# SCH_mosfet_driver_copy_2022-10-09.net
KiCad netlist of a schematic drawn in EasyEDA
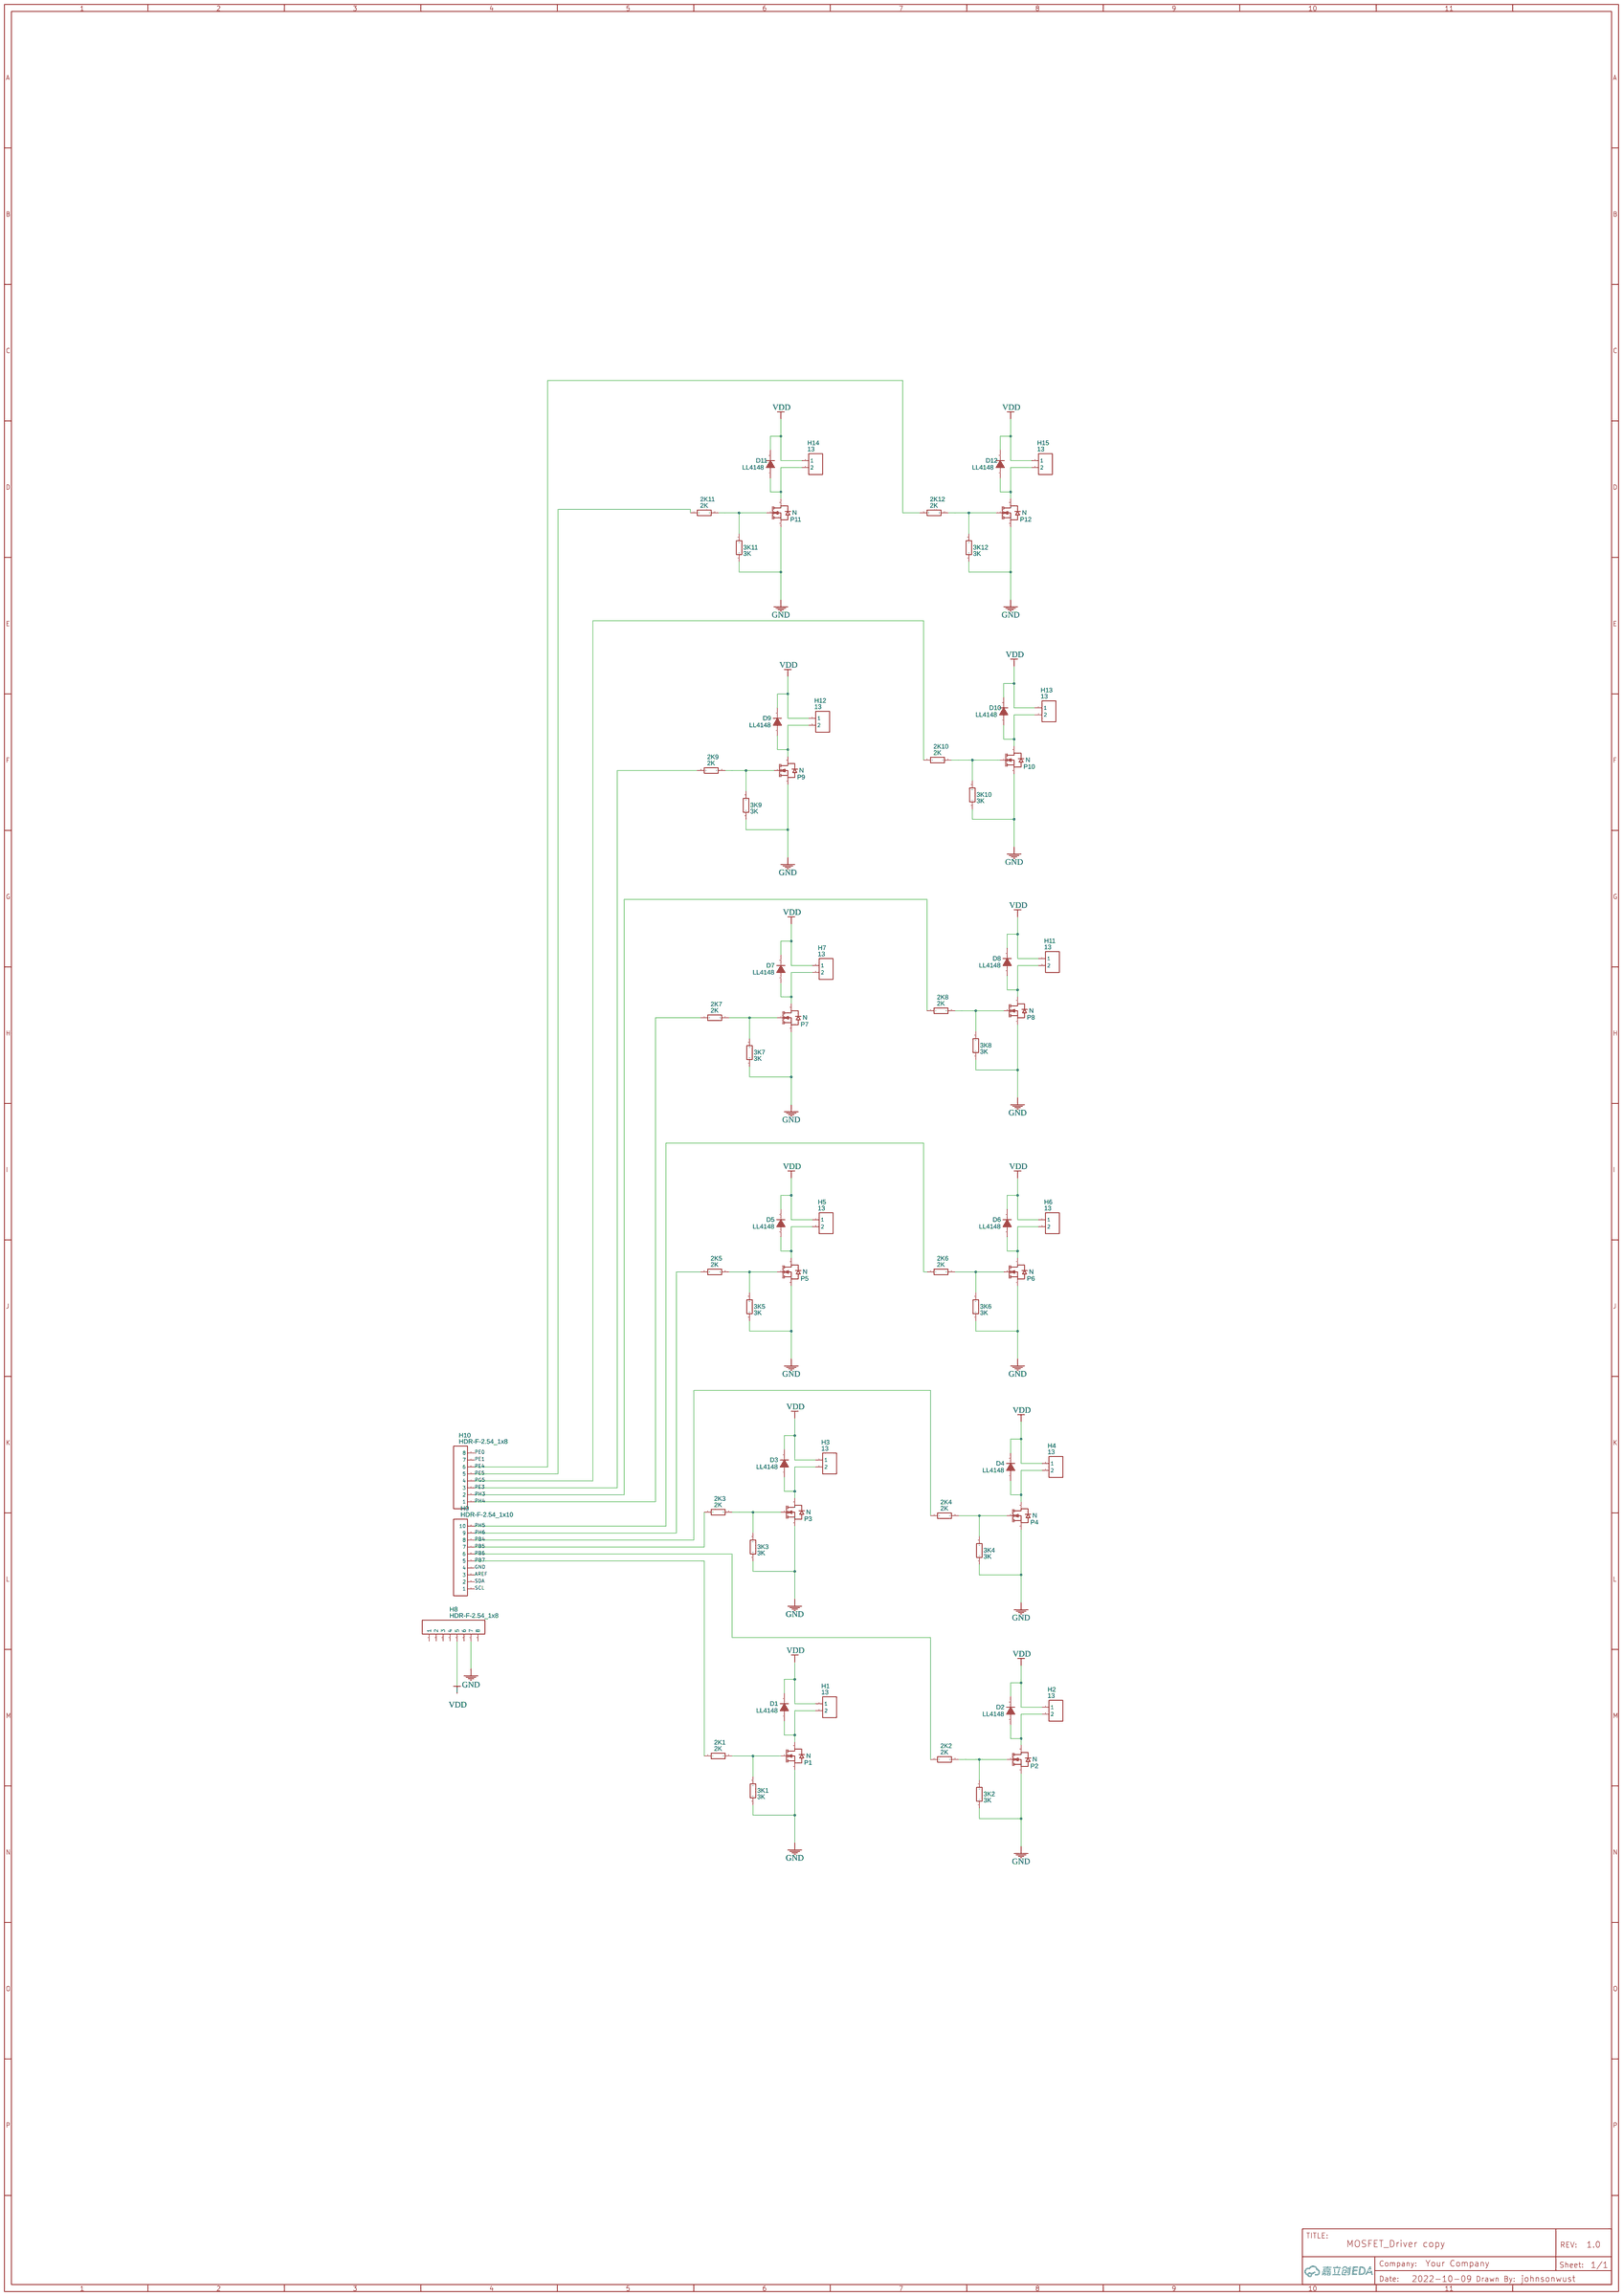
[diagram p0: schematic sheet]

(export (version "E")
  (design (tool "Eeschema 10.0.6"))
  (components
    (comp (ref "2K1")
      (value "2K")
      (fields
        (field (name "BOM_Manufacturer Part") "0805W8F1003T5E")
        (field (name "BOM_Supplier Part") "C17407")
      )
      (libsource (lib "") (part "0805W8F1003T5E"))
    )
    (comp (ref "2K2")
      (value "2K")
      (fields
        (field (name "BOM_Manufacturer Part") "0805W8F1003T5E")
        (field (name "BOM_Supplier Part") "C17407")
      )
      (libsource (lib "") (part "0805W8F1003T5E"))
    )
    (comp (ref "2K3")
      (value "2K")
      (fields
        (field (name "BOM_Manufacturer Part") "0805W8F1003T5E")
        (field (name "BOM_Supplier Part") "C17407")
      )
      (libsource (lib "") (part "0805W8F1003T5E"))
    )
    (comp (ref "2K4")
      (value "2K")
      (fields
        (field (name "BOM_Manufacturer Part") "0805W8F1003T5E")
        (field (name "BOM_Supplier Part") "C17407")
      )
      (libsource (lib "") (part "0805W8F1003T5E"))
    )
    (comp (ref "2K5")
      (value "2K")
      (fields
        (field (name "BOM_Manufacturer Part") "0805W8F1003T5E")
        (field (name "BOM_Supplier Part") "C17407")
      )
      (libsource (lib "") (part "0805W8F1003T5E"))
    )
    (comp (ref "2K6")
      (value "2K")
      (fields
        (field (name "BOM_Manufacturer Part") "0805W8F1003T5E")
        (field (name "BOM_Supplier Part") "C17407")
      )
      (libsource (lib "") (part "0805W8F1003T5E"))
    )
    (comp (ref "2K7")
      (value "2K")
      (fields
        (field (name "BOM_Manufacturer Part") "0805W8F1003T5E")
        (field (name "BOM_Supplier Part") "C17407")
      )
      (libsource (lib "") (part "0805W8F1003T5E"))
    )
    (comp (ref "2K8")
      (value "2K")
      (fields
        (field (name "BOM_Manufacturer Part") "0805W8F1003T5E")
        (field (name "BOM_Supplier Part") "C17407")
      )
      (libsource (lib "") (part "0805W8F1003T5E"))
    )
    (comp (ref "2K9")
      (value "2K")
      (fields
        (field (name "BOM_Manufacturer Part") "0805W8F1003T5E")
        (field (name "BOM_Supplier Part") "C17407")
      )
      (libsource (lib "") (part "0805W8F1003T5E"))
    )
    (comp (ref "2K10")
      (value "2K")
      (fields
        (field (name "BOM_Manufacturer Part") "0805W8F1003T5E")
        (field (name "BOM_Supplier Part") "C17407")
      )
      (libsource (lib "") (part "0805W8F1003T5E"))
    )
    (comp (ref "2K11")
      (value "2K")
      (fields
        (field (name "BOM_Manufacturer Part") "0805W8F1003T5E")
        (field (name "BOM_Supplier Part") "C17407")
      )
      (libsource (lib "") (part "0805W8F1003T5E"))
    )
    (comp (ref "2K12")
      (value "2K")
      (fields
        (field (name "BOM_Manufacturer Part") "0805W8F1003T5E")
        (field (name "BOM_Supplier Part") "C17407")
      )
      (libsource (lib "") (part "0805W8F1003T5E"))
    )
    (comp (ref "3K1")
      (value "3K")
      (fields
        (field (name "BOM_Manufacturer Part") "0805W8F1001T5E")
        (field (name "BOM_Supplier Part") "C17513")
      )
      (libsource (lib "") (part "0805W8F1001T5E"))
    )
    (comp (ref "3K2")
      (value "3K")
      (fields
        (field (name "BOM_Manufacturer Part") "0805W8F1001T5E")
        (field (name "BOM_Supplier Part") "C17513")
      )
      (libsource (lib "") (part "0805W8F1001T5E"))
    )
    (comp (ref "3K3")
      (value "3K")
      (fields
        (field (name "BOM_Manufacturer Part") "0805W8F1001T5E")
        (field (name "BOM_Supplier Part") "C17513")
      )
      (libsource (lib "") (part "0805W8F1001T5E"))
    )
    (comp (ref "3K4")
      (value "3K")
      (fields
        (field (name "BOM_Manufacturer Part") "0805W8F1001T5E")
        (field (name "BOM_Supplier Part") "C17513")
      )
      (libsource (lib "") (part "0805W8F1001T5E"))
    )
    (comp (ref "3K5")
      (value "3K")
      (fields
        (field (name "BOM_Manufacturer Part") "0805W8F1001T5E")
        (field (name "BOM_Supplier Part") "C17513")
      )
      (libsource (lib "") (part "0805W8F1001T5E"))
    )
    (comp (ref "3K6")
      (value "3K")
      (fields
        (field (name "BOM_Manufacturer Part") "0805W8F1001T5E")
        (field (name "BOM_Supplier Part") "C17513")
      )
      (libsource (lib "") (part "0805W8F1001T5E"))
    )
    (comp (ref "3K7")
      (value "3K")
      (fields
        (field (name "BOM_Manufacturer Part") "0805W8F1001T5E")
        (field (name "BOM_Supplier Part") "C17513")
      )
      (libsource (lib "") (part "0805W8F1001T5E"))
    )
    (comp (ref "3K8")
      (value "3K")
      (fields
        (field (name "BOM_Manufacturer Part") "0805W8F1001T5E")
        (field (name "BOM_Supplier Part") "C17513")
      )
      (libsource (lib "") (part "0805W8F1001T5E"))
    )
    (comp (ref "3K9")
      (value "3K")
      (fields
        (field (name "BOM_Manufacturer Part") "0805W8F1001T5E")
        (field (name "BOM_Supplier Part") "C17513")
      )
      (libsource (lib "") (part "0805W8F1001T5E"))
    )
    (comp (ref "3K10")
      (value "3K")
      (fields
        (field (name "BOM_Manufacturer Part") "0805W8F1001T5E")
        (field (name "BOM_Supplier Part") "C17513")
      )
      (libsource (lib "") (part "0805W8F1001T5E"))
    )
    (comp (ref "3K11")
      (value "3K")
      (fields
        (field (name "BOM_Manufacturer Part") "0805W8F1001T5E")
        (field (name "BOM_Supplier Part") "C17513")
      )
      (libsource (lib "") (part "0805W8F1001T5E"))
    )
    (comp (ref "3K12")
      (value "3K")
      (fields
        (field (name "BOM_Manufacturer Part") "0805W8F1001T5E")
        (field (name "BOM_Supplier Part") "C17513")
      )
      (libsource (lib "") (part "0805W8F1001T5E"))
    )
    (comp (ref "D1")
      (value "LL4148")
      (fields (field (name "BOM_Supplier Part") "C9808"))
      (libsource (lib "") (part "LL4148"))
    )
    (comp (ref "D2")
      (value "LL4148")
      (fields (field (name "BOM_Supplier Part") "C9808"))
      (libsource (lib "") (part "LL4148"))
    )
    (comp (ref "D3")
      (value "LL4148")
      (fields (field (name "BOM_Supplier Part") "C9808"))
      (libsource (lib "") (part "LL4148"))
    )
    (comp (ref "D4")
      (value "LL4148")
      (fields (field (name "BOM_Supplier Part") "C9808"))
      (libsource (lib "") (part "LL4148"))
    )
    (comp (ref "D5")
      (value "LL4148")
      (fields (field (name "BOM_Supplier Part") "C9808"))
      (libsource (lib "") (part "LL4148"))
    )
    (comp (ref "D6")
      (value "LL4148")
      (fields (field (name "BOM_Supplier Part") "C9808"))
      (libsource (lib "") (part "LL4148"))
    )
    (comp (ref "D7")
      (value "LL4148")
      (fields (field (name "BOM_Supplier Part") "C9808"))
      (libsource (lib "") (part "LL4148"))
    )
    (comp (ref "D8")
      (value "LL4148")
      (fields (field (name "BOM_Supplier Part") "C9808"))
      (libsource (lib "") (part "LL4148"))
    )
    (comp (ref "D9")
      (value "LL4148")
      (fields (field (name "BOM_Supplier Part") "C9808"))
      (libsource (lib "") (part "LL4148"))
    )
    (comp (ref "D10")
      (value "LL4148")
      (fields (field (name "BOM_Supplier Part") "C9808"))
      (libsource (lib "") (part "LL4148"))
    )
    (comp (ref "D11")
      (value "LL4148")
      (fields (field (name "BOM_Supplier Part") "C9808"))
      (libsource (lib "") (part "LL4148"))
    )
    (comp (ref "D12")
      (value "LL4148")
      (fields (field (name "BOM_Supplier Part") "C9808"))
      (libsource (lib "") (part "LL4148"))
    )
    (comp (ref "H1")
      (value "13")
      (fields (field (name "BOM_Supplier Part") "C49661"))
      (libsource (lib "") (part "HDR-F-2.54_1x2"))
    )
    (comp (ref "H2")
      (value "13")
      (fields (field (name "BOM_Supplier Part") "C49661"))
      (libsource (lib "") (part "HDR-F-2.54_1x2"))
    )
    (comp (ref "H3")
      (value "13")
      (fields (field (name "BOM_Supplier Part") "C49661"))
      (libsource (lib "") (part "HDR-F-2.54_1x2"))
    )
    (comp (ref "H4")
      (value "13")
      (fields (field (name "BOM_Supplier Part") "C49661"))
      (libsource (lib "") (part "HDR-F-2.54_1x2"))
    )
    (comp (ref "H5")
      (value "13")
      (fields (field (name "BOM_Supplier Part") "C49661"))
      (libsource (lib "") (part "HDR-F-2.54_1x2"))
    )
    (comp (ref "H6")
      (value "13")
      (fields (field (name "BOM_Supplier Part") "C49661"))
      (libsource (lib "") (part "HDR-F-2.54_1x2"))
    )
    (comp (ref "H7")
      (value "13")
      (fields (field (name "BOM_Supplier Part") "C49661"))
      (libsource (lib "") (part "HDR-F-2.54_1x2"))
    )
    (comp (ref "H8")
      (value "HDR-F-2.54_1x8")
      (fields (field (name "BOM_Supplier Part") "C225505"))
      (libsource (lib "") (part "HDR-F-2.54_1x8"))
    )
    (comp (ref "H9")
      (value "HDR-F-2.54_1x10")
      (fields (field (name "BOM_Supplier Part") "C35445"))
      (libsource (lib "") (part "HDR-F-2.54_1x10"))
    )
    (comp (ref "H10")
      (value "HDR-F-2.54_1x8")
      (fields (field (name "BOM_Supplier Part") "C225505"))
      (libsource (lib "") (part "HDR-F-2.54_1x8_1"))
    )
    (comp (ref "H11")
      (value "13")
      (fields (field (name "BOM_Supplier Part") "C49661"))
      (libsource (lib "") (part "HDR-F-2.54_1x2"))
    )
    (comp (ref "H12")
      (value "13")
      (fields (field (name "BOM_Supplier Part") "C49661"))
      (libsource (lib "") (part "HDR-F-2.54_1x2"))
    )
    (comp (ref "H13")
      (value "13")
      (fields (field (name "BOM_Supplier Part") "C49661"))
      (libsource (lib "") (part "HDR-F-2.54_1x2"))
    )
    (comp (ref "H14")
      (value "13")
      (fields (field (name "BOM_Supplier Part") "C49661"))
      (libsource (lib "") (part "HDR-F-2.54_1x2"))
    )
    (comp (ref "H15")
      (value "13")
      (fields (field (name "BOM_Supplier Part") "C49661"))
      (libsource (lib "") (part "HDR-F-2.54_1x2"))
    )
    (comp (ref "P1")
      (value "N")
      (fields (field (name "BOM_Manufacturer Part") "BSS138") (field (name "BOM_Supplier Part") "C779768"))
      (libsource (lib "") (part "BSS138_C779768"))
    )
    (comp (ref "P2")
      (value "N")
      (fields (field (name "BOM_Manufacturer Part") "BSS138") (field (name "BOM_Supplier Part") "C779768"))
      (libsource (lib "") (part "BSS138_C779768"))
    )
    (comp (ref "P3")
      (value "N")
      (fields (field (name "BOM_Manufacturer Part") "BSS138") (field (name "BOM_Supplier Part") "C779768"))
      (libsource (lib "") (part "BSS138_C779768"))
    )
    (comp (ref "P4")
      (value "N")
      (fields (field (name "BOM_Manufacturer Part") "BSS138") (field (name "BOM_Supplier Part") "C779768"))
      (libsource (lib "") (part "BSS138_C779768"))
    )
    (comp (ref "P5")
      (value "N")
      (fields (field (name "BOM_Manufacturer Part") "BSS138") (field (name "BOM_Supplier Part") "C779768"))
      (libsource (lib "") (part "BSS138_C779768"))
    )
    (comp (ref "P6")
      (value "N")
      (fields (field (name "BOM_Manufacturer Part") "BSS138") (field (name "BOM_Supplier Part") "C779768"))
      (libsource (lib "") (part "BSS138_C779768"))
    )
    (comp (ref "P7")
      (value "N")
      (fields (field (name "BOM_Manufacturer Part") "BSS138") (field (name "BOM_Supplier Part") "C779768"))
      (libsource (lib "") (part "BSS138_C779768"))
    )
    (comp (ref "P8")
      (value "N")
      (fields (field (name "BOM_Manufacturer Part") "BSS138") (field (name "BOM_Supplier Part") "C779768"))
      (libsource (lib "") (part "BSS138_C779768"))
    )
    (comp (ref "P9")
      (value "N")
      (fields (field (name "BOM_Manufacturer Part") "BSS138") (field (name "BOM_Supplier Part") "C779768"))
      (libsource (lib "") (part "BSS138_C779768"))
    )
    (comp (ref "P10")
      (value "N")
      (fields (field (name "BOM_Manufacturer Part") "BSS138") (field (name "BOM_Supplier Part") "C779768"))
      (libsource (lib "") (part "BSS138_C779768"))
    )
    (comp (ref "P11")
      (value "N")
      (fields (field (name "BOM_Manufacturer Part") "BSS138") (field (name "BOM_Supplier Part") "C779768"))
      (libsource (lib "") (part "BSS138_C779768"))
    )
    (comp (ref "P12")
      (value "N")
      (fields (field (name "BOM_Manufacturer Part") "BSS138") (field (name "BOM_Supplier Part") "C779768"))
      (libsource (lib "") (part "BSS138_C779768"))
    )
  )
  (nets
    (net (code "1") (name "/AREF") (class "Default")
      (node (ref "H9") (pin "3") (pinfunction "3_3") (pintype "unspecified"))
    )
    (net (code "2") (name "/PB4") (class "Default")
      (node (ref "2K4") (pin "1") (pinfunction "1_1") (pintype "input"))
      (node (ref "H9") (pin "8") (pinfunction "8_8") (pintype "unspecified"))
    )
    (net (code "3") (name "/PB5") (class "Default")
      (node (ref "2K3") (pin "1") (pinfunction "1_1") (pintype "input"))
      (node (ref "H9") (pin "7") (pinfunction "7_7") (pintype "unspecified"))
    )
    (net (code "4") (name "/PB6") (class "Default")
      (node (ref "2K2") (pin "1") (pinfunction "1_1") (pintype "input"))
      (node (ref "H9") (pin "6") (pinfunction "6_6") (pintype "unspecified"))
    )
    (net (code "5") (name "/PB7") (class "Default")
      (node (ref "2K1") (pin "1") (pinfunction "1_1") (pintype "input"))
      (node (ref "H9") (pin "5") (pinfunction "5_5") (pintype "unspecified"))
    )
    (net (code "6") (name "/PE0") (class "Default")
      (node (ref "H10") (pin "8") (pinfunction "8_8") (pintype "unspecified"))
    )
    (net (code "7") (name "/PE1") (class "Default")
      (node (ref "H10") (pin "7") (pinfunction "7_7") (pintype "unspecified"))
    )
    (net (code "8") (name "/PE3") (class "Default")
      (node (ref "2K9") (pin "1") (pinfunction "1_1") (pintype "input"))
      (node (ref "H10") (pin "3") (pinfunction "3_3") (pintype "unspecified"))
    )
    (net (code "9") (name "/PE4") (class "Default")
      (node (ref "2K12") (pin "1") (pinfunction "1_1") (pintype "input"))
      (node (ref "H10") (pin "6") (pinfunction "6_6") (pintype "unspecified"))
    )
    (net (code "10") (name "/PE5") (class "Default")
      (node (ref "2K11") (pin "1") (pinfunction "1_1") (pintype "input"))
      (node (ref "H10") (pin "5") (pinfunction "5_5") (pintype "unspecified"))
    )
    (net (code "11") (name "/PG5") (class "Default")
      (node (ref "2K10") (pin "1") (pinfunction "1_1") (pintype "input"))
      (node (ref "H10") (pin "4") (pinfunction "4_4") (pintype "unspecified"))
    )
    (net (code "12") (name "/PH3") (class "Default")
      (node (ref "2K8") (pin "1") (pinfunction "1_1") (pintype "input"))
      (node (ref "H10") (pin "2") (pinfunction "2_2") (pintype "unspecified"))
    )
    (net (code "13") (name "/PH4") (class "Default")
      (node (ref "2K7") (pin "1") (pinfunction "1_1") (pintype "input"))
      (node (ref "H10") (pin "1") (pinfunction "1_1") (pintype "unspecified"))
    )
    (net (code "14") (name "/PH5") (class "Default")
      (node (ref "2K6") (pin "1") (pinfunction "1_1") (pintype "input"))
      (node (ref "H9") (pin "10") (pinfunction "10_10") (pintype "unspecified"))
    )
    (net (code "15") (name "/PH6") (class "Default")
      (node (ref "2K5") (pin "1") (pinfunction "1_1") (pintype "input"))
      (node (ref "H9") (pin "9") (pinfunction "9_9") (pintype "unspecified"))
    )
    (net (code "16") (name "/SCL") (class "Default")
      (node (ref "H9") (pin "1") (pinfunction "1_1") (pintype "unspecified"))
    )
    (net (code "17") (name "/SDA") (class "Default")
      (node (ref "H9") (pin "2") (pinfunction "2_2") (pintype "unspecified"))
    )
    (net (code "18") (name "GND") (class "Default")
      (node (ref "3K1") (pin "1") (pinfunction "1_1") (pintype "input"))
      (node (ref "3K10") (pin "1") (pinfunction "1_1") (pintype "input"))
      (node (ref "3K11") (pin "1") (pinfunction "1_1") (pintype "input"))
      (node (ref "3K12") (pin "1") (pinfunction "1_1") (pintype "input"))
      (node (ref "3K2") (pin "1") (pinfunction "1_1") (pintype "input"))
      (node (ref "3K3") (pin "1") (pinfunction "1_1") (pintype "input"))
      (node (ref "3K4") (pin "1") (pinfunction "1_1") (pintype "input"))
      (node (ref "3K5") (pin "1") (pinfunction "1_1") (pintype "input"))
      (node (ref "3K6") (pin "1") (pinfunction "1_1") (pintype "input"))
      (node (ref "3K7") (pin "1") (pinfunction "1_1") (pintype "input"))
      (node (ref "3K8") (pin "1") (pinfunction "1_1") (pintype "input"))
      (node (ref "3K9") (pin "1") (pinfunction "1_1") (pintype "input"))
      (node (ref "H8") (pin "7") (pinfunction "7_7") (pintype "unspecified"))
      (node (ref "H9") (pin "4") (pinfunction "4_4") (pintype "unspecified"))
      (node (ref "P1") (pin "2") (pinfunction "S_2") (pintype "unspecified"))
      (node (ref "P10") (pin "2") (pinfunction "S_2") (pintype "unspecified"))
      (node (ref "P11") (pin "2") (pinfunction "S_2") (pintype "unspecified"))
      (node (ref "P12") (pin "2") (pinfunction "S_2") (pintype "unspecified"))
      (node (ref "P2") (pin "2") (pinfunction "S_2") (pintype "unspecified"))
      (node (ref "P3") (pin "2") (pinfunction "S_2") (pintype "unspecified"))
      (node (ref "P4") (pin "2") (pinfunction "S_2") (pintype "unspecified"))
      (node (ref "P5") (pin "2") (pinfunction "S_2") (pintype "unspecified"))
      (node (ref "P6") (pin "2") (pinfunction "S_2") (pintype "unspecified"))
      (node (ref "P7") (pin "2") (pinfunction "S_2") (pintype "unspecified"))
      (node (ref "P8") (pin "2") (pinfunction "S_2") (pintype "unspecified"))
      (node (ref "P9") (pin "2") (pinfunction "S_2") (pintype "unspecified"))
    )
    (net (code "19") (name "Net-(D1-A)") (class "Default")
      (node (ref "D1") (pin "1") (pinfunction "A_1") (pintype "unspecified"))
      (node (ref "H1") (pin "2") (pinfunction "2_2") (pintype "input"))
      (node (ref "P1") (pin "3") (pinfunction "D_3") (pintype "unspecified"))
    )
    (net (code "20") (name "Net-(D2-A)") (class "Default")
      (node (ref "D2") (pin "1") (pinfunction "A_1") (pintype "unspecified"))
      (node (ref "H2") (pin "2") (pinfunction "2_2") (pintype "input"))
      (node (ref "P2") (pin "3") (pinfunction "D_3") (pintype "unspecified"))
    )
    (net (code "21") (name "Net-(D3-A)") (class "Default")
      (node (ref "D3") (pin "1") (pinfunction "A_1") (pintype "unspecified"))
      (node (ref "H3") (pin "2") (pinfunction "2_2") (pintype "input"))
      (node (ref "P3") (pin "3") (pinfunction "D_3") (pintype "unspecified"))
    )
    (net (code "22") (name "Net-(D4-A)") (class "Default")
      (node (ref "D4") (pin "1") (pinfunction "A_1") (pintype "unspecified"))
      (node (ref "H4") (pin "2") (pinfunction "2_2") (pintype "input"))
      (node (ref "P4") (pin "3") (pinfunction "D_3") (pintype "unspecified"))
    )
    (net (code "23") (name "Net-(D5-A)") (class "Default")
      (node (ref "D5") (pin "1") (pinfunction "A_1") (pintype "unspecified"))
      (node (ref "H5") (pin "2") (pinfunction "2_2") (pintype "input"))
      (node (ref "P5") (pin "3") (pinfunction "D_3") (pintype "unspecified"))
    )
    (net (code "24") (name "Net-(D6-A)") (class "Default")
      (node (ref "D6") (pin "1") (pinfunction "A_1") (pintype "unspecified"))
      (node (ref "H6") (pin "2") (pinfunction "2_2") (pintype "input"))
      (node (ref "P6") (pin "3") (pinfunction "D_3") (pintype "unspecified"))
    )
    (net (code "25") (name "Net-(D7-A)") (class "Default")
      (node (ref "D7") (pin "1") (pinfunction "A_1") (pintype "unspecified"))
      (node (ref "H7") (pin "2") (pinfunction "2_2") (pintype "input"))
      (node (ref "P7") (pin "3") (pinfunction "D_3") (pintype "unspecified"))
    )
    (net (code "26") (name "Net-(D8-A)") (class "Default")
      (node (ref "D8") (pin "1") (pinfunction "A_1") (pintype "unspecified"))
      (node (ref "H11") (pin "2") (pinfunction "2_2") (pintype "input"))
      (node (ref "P8") (pin "3") (pinfunction "D_3") (pintype "unspecified"))
    )
    (net (code "27") (name "Net-(D9-A)") (class "Default")
      (node (ref "D9") (pin "1") (pinfunction "A_1") (pintype "unspecified"))
      (node (ref "H12") (pin "2") (pinfunction "2_2") (pintype "input"))
      (node (ref "P9") (pin "3") (pinfunction "D_3") (pintype "unspecified"))
    )
    (net (code "28") (name "Net-(D10-A)") (class "Default")
      (node (ref "D10") (pin "1") (pinfunction "A_1") (pintype "unspecified"))
      (node (ref "H13") (pin "2") (pinfunction "2_2") (pintype "input"))
      (node (ref "P10") (pin "3") (pinfunction "D_3") (pintype "unspecified"))
    )
    (net (code "29") (name "Net-(D11-A)") (class "Default")
      (node (ref "D11") (pin "1") (pinfunction "A_1") (pintype "unspecified"))
      (node (ref "H14") (pin "2") (pinfunction "2_2") (pintype "input"))
      (node (ref "P11") (pin "3") (pinfunction "D_3") (pintype "unspecified"))
    )
    (net (code "30") (name "Net-(D12-A)") (class "Default")
      (node (ref "D12") (pin "1") (pinfunction "A_1") (pintype "unspecified"))
      (node (ref "H15") (pin "2") (pinfunction "2_2") (pintype "input"))
      (node (ref "P12") (pin "3") (pinfunction "D_3") (pintype "unspecified"))
    )
    (net (code "31") (name "Net-(P1-G)") (class "Default")
      (node (ref "2K1") (pin "2") (pinfunction "2_2") (pintype "input"))
      (node (ref "3K1") (pin "2") (pinfunction "2_2") (pintype "input"))
      (node (ref "P1") (pin "1") (pinfunction "G_1") (pintype "unspecified"))
    )
    (net (code "32") (name "Net-(P2-G)") (class "Default")
      (node (ref "2K2") (pin "2") (pinfunction "2_2") (pintype "input"))
      (node (ref "3K2") (pin "2") (pinfunction "2_2") (pintype "input"))
      (node (ref "P2") (pin "1") (pinfunction "G_1") (pintype "unspecified"))
    )
    (net (code "33") (name "Net-(P3-G)") (class "Default")
      (node (ref "2K3") (pin "2") (pinfunction "2_2") (pintype "input"))
      (node (ref "3K3") (pin "2") (pinfunction "2_2") (pintype "input"))
      (node (ref "P3") (pin "1") (pinfunction "G_1") (pintype "unspecified"))
    )
    (net (code "34") (name "Net-(P4-G)") (class "Default")
      (node (ref "2K4") (pin "2") (pinfunction "2_2") (pintype "input"))
      (node (ref "3K4") (pin "2") (pinfunction "2_2") (pintype "input"))
      (node (ref "P4") (pin "1") (pinfunction "G_1") (pintype "unspecified"))
    )
    (net (code "35") (name "Net-(P5-G)") (class "Default")
      (node (ref "2K5") (pin "2") (pinfunction "2_2") (pintype "input"))
      (node (ref "3K5") (pin "2") (pinfunction "2_2") (pintype "input"))
      (node (ref "P5") (pin "1") (pinfunction "G_1") (pintype "unspecified"))
    )
    (net (code "36") (name "Net-(P6-G)") (class "Default")
      (node (ref "2K6") (pin "2") (pinfunction "2_2") (pintype "input"))
      (node (ref "3K6") (pin "2") (pinfunction "2_2") (pintype "input"))
      (node (ref "P6") (pin "1") (pinfunction "G_1") (pintype "unspecified"))
    )
    (net (code "37") (name "Net-(P7-G)") (class "Default")
      (node (ref "2K7") (pin "2") (pinfunction "2_2") (pintype "input"))
      (node (ref "3K7") (pin "2") (pinfunction "2_2") (pintype "input"))
      (node (ref "P7") (pin "1") (pinfunction "G_1") (pintype "unspecified"))
    )
    (net (code "38") (name "Net-(P8-G)") (class "Default")
      (node (ref "2K8") (pin "2") (pinfunction "2_2") (pintype "input"))
      (node (ref "3K8") (pin "2") (pinfunction "2_2") (pintype "input"))
      (node (ref "P8") (pin "1") (pinfunction "G_1") (pintype "unspecified"))
    )
    (net (code "39") (name "Net-(P9-G)") (class "Default")
      (node (ref "2K9") (pin "2") (pinfunction "2_2") (pintype "input"))
      (node (ref "3K9") (pin "2") (pinfunction "2_2") (pintype "input"))
      (node (ref "P9") (pin "1") (pinfunction "G_1") (pintype "unspecified"))
    )
    (net (code "40") (name "Net-(P10-G)") (class "Default")
      (node (ref "2K10") (pin "2") (pinfunction "2_2") (pintype "input"))
      (node (ref "3K10") (pin "2") (pinfunction "2_2") (pintype "input"))
      (node (ref "P10") (pin "1") (pinfunction "G_1") (pintype "unspecified"))
    )
    (net (code "41") (name "Net-(P11-G)") (class "Default")
      (node (ref "2K11") (pin "2") (pinfunction "2_2") (pintype "input"))
      (node (ref "3K11") (pin "2") (pinfunction "2_2") (pintype "input"))
      (node (ref "P11") (pin "1") (pinfunction "G_1") (pintype "unspecified"))
    )
    (net (code "42") (name "Net-(P12-G)") (class "Default")
      (node (ref "2K12") (pin "2") (pinfunction "2_2") (pintype "input"))
      (node (ref "3K12") (pin "2") (pinfunction "2_2") (pintype "input"))
      (node (ref "P12") (pin "1") (pinfunction "G_1") (pintype "unspecified"))
    )
    (net (code "43") (name "VDD") (class "Default")
      (node (ref "D1") (pin "2") (pinfunction "K_2") (pintype "unspecified"))
      (node (ref "D10") (pin "2") (pinfunction "K_2") (pintype "unspecified"))
      (node (ref "D11") (pin "2") (pinfunction "K_2") (pintype "unspecified"))
      (node (ref "D12") (pin "2") (pinfunction "K_2") (pintype "unspecified"))
      (node (ref "D2") (pin "2") (pinfunction "K_2") (pintype "unspecified"))
      (node (ref "D3") (pin "2") (pinfunction "K_2") (pintype "unspecified"))
      (node (ref "D4") (pin "2") (pinfunction "K_2") (pintype "unspecified"))
      (node (ref "D5") (pin "2") (pinfunction "K_2") (pintype "unspecified"))
      (node (ref "D6") (pin "2") (pinfunction "K_2") (pintype "unspecified"))
      (node (ref "D7") (pin "2") (pinfunction "K_2") (pintype "unspecified"))
      (node (ref "D8") (pin "2") (pinfunction "K_2") (pintype "unspecified"))
      (node (ref "D9") (pin "2") (pinfunction "K_2") (pintype "unspecified"))
      (node (ref "H1") (pin "1") (pinfunction "1_1") (pintype "input"))
      (node (ref "H11") (pin "1") (pinfunction "1_1") (pintype "input"))
      (node (ref "H12") (pin "1") (pinfunction "1_1") (pintype "input"))
      (node (ref "H13") (pin "1") (pinfunction "1_1") (pintype "input"))
      (node (ref "H14") (pin "1") (pinfunction "1_1") (pintype "input"))
      (node (ref "H15") (pin "1") (pinfunction "1_1") (pintype "input"))
      (node (ref "H2") (pin "1") (pinfunction "1_1") (pintype "input"))
      (node (ref "H3") (pin "1") (pinfunction "1_1") (pintype "input"))
      (node (ref "H4") (pin "1") (pinfunction "1_1") (pintype "input"))
      (node (ref "H5") (pin "1") (pinfunction "1_1") (pintype "input"))
      (node (ref "H6") (pin "1") (pinfunction "1_1") (pintype "input"))
      (node (ref "H7") (pin "1") (pinfunction "1_1") (pintype "input"))
      (node (ref "H8") (pin "5") (pinfunction "5_5") (pintype "unspecified"))
    )
    (net (code "44") (name "unconnected-(H8-Pad1)") (class "Default")
      (node (ref "H8") (pin "1") (pinfunction "1_1") (pintype "unspecified"))
    )
    (net (code "45") (name "unconnected-(H8-Pad2)") (class "Default")
      (node (ref "H8") (pin "2") (pinfunction "2_2") (pintype "unspecified"))
    )
    (net (code "46") (name "unconnected-(H8-Pad3)") (class "Default")
      (node (ref "H8") (pin "3") (pinfunction "3_3") (pintype "unspecified"))
    )
    (net (code "47") (name "unconnected-(H8-Pad4)") (class "Default")
      (node (ref "H8") (pin "4") (pinfunction "4_4") (pintype "unspecified"))
    )
    (net (code "48") (name "unconnected-(H8-Pad6)") (class "Default")
      (node (ref "H8") (pin "6") (pinfunction "6_6") (pintype "unspecified"))
    )
    (net (code "49") (name "unconnected-(H8-Pad8)") (class "Default")
      (node (ref "H8") (pin "8") (pinfunction "8_8") (pintype "unspecified"))
    )
  )
)
